# Fri3D_2024_00.net
KiCad netlist of a schematic drawn in Altium Designer
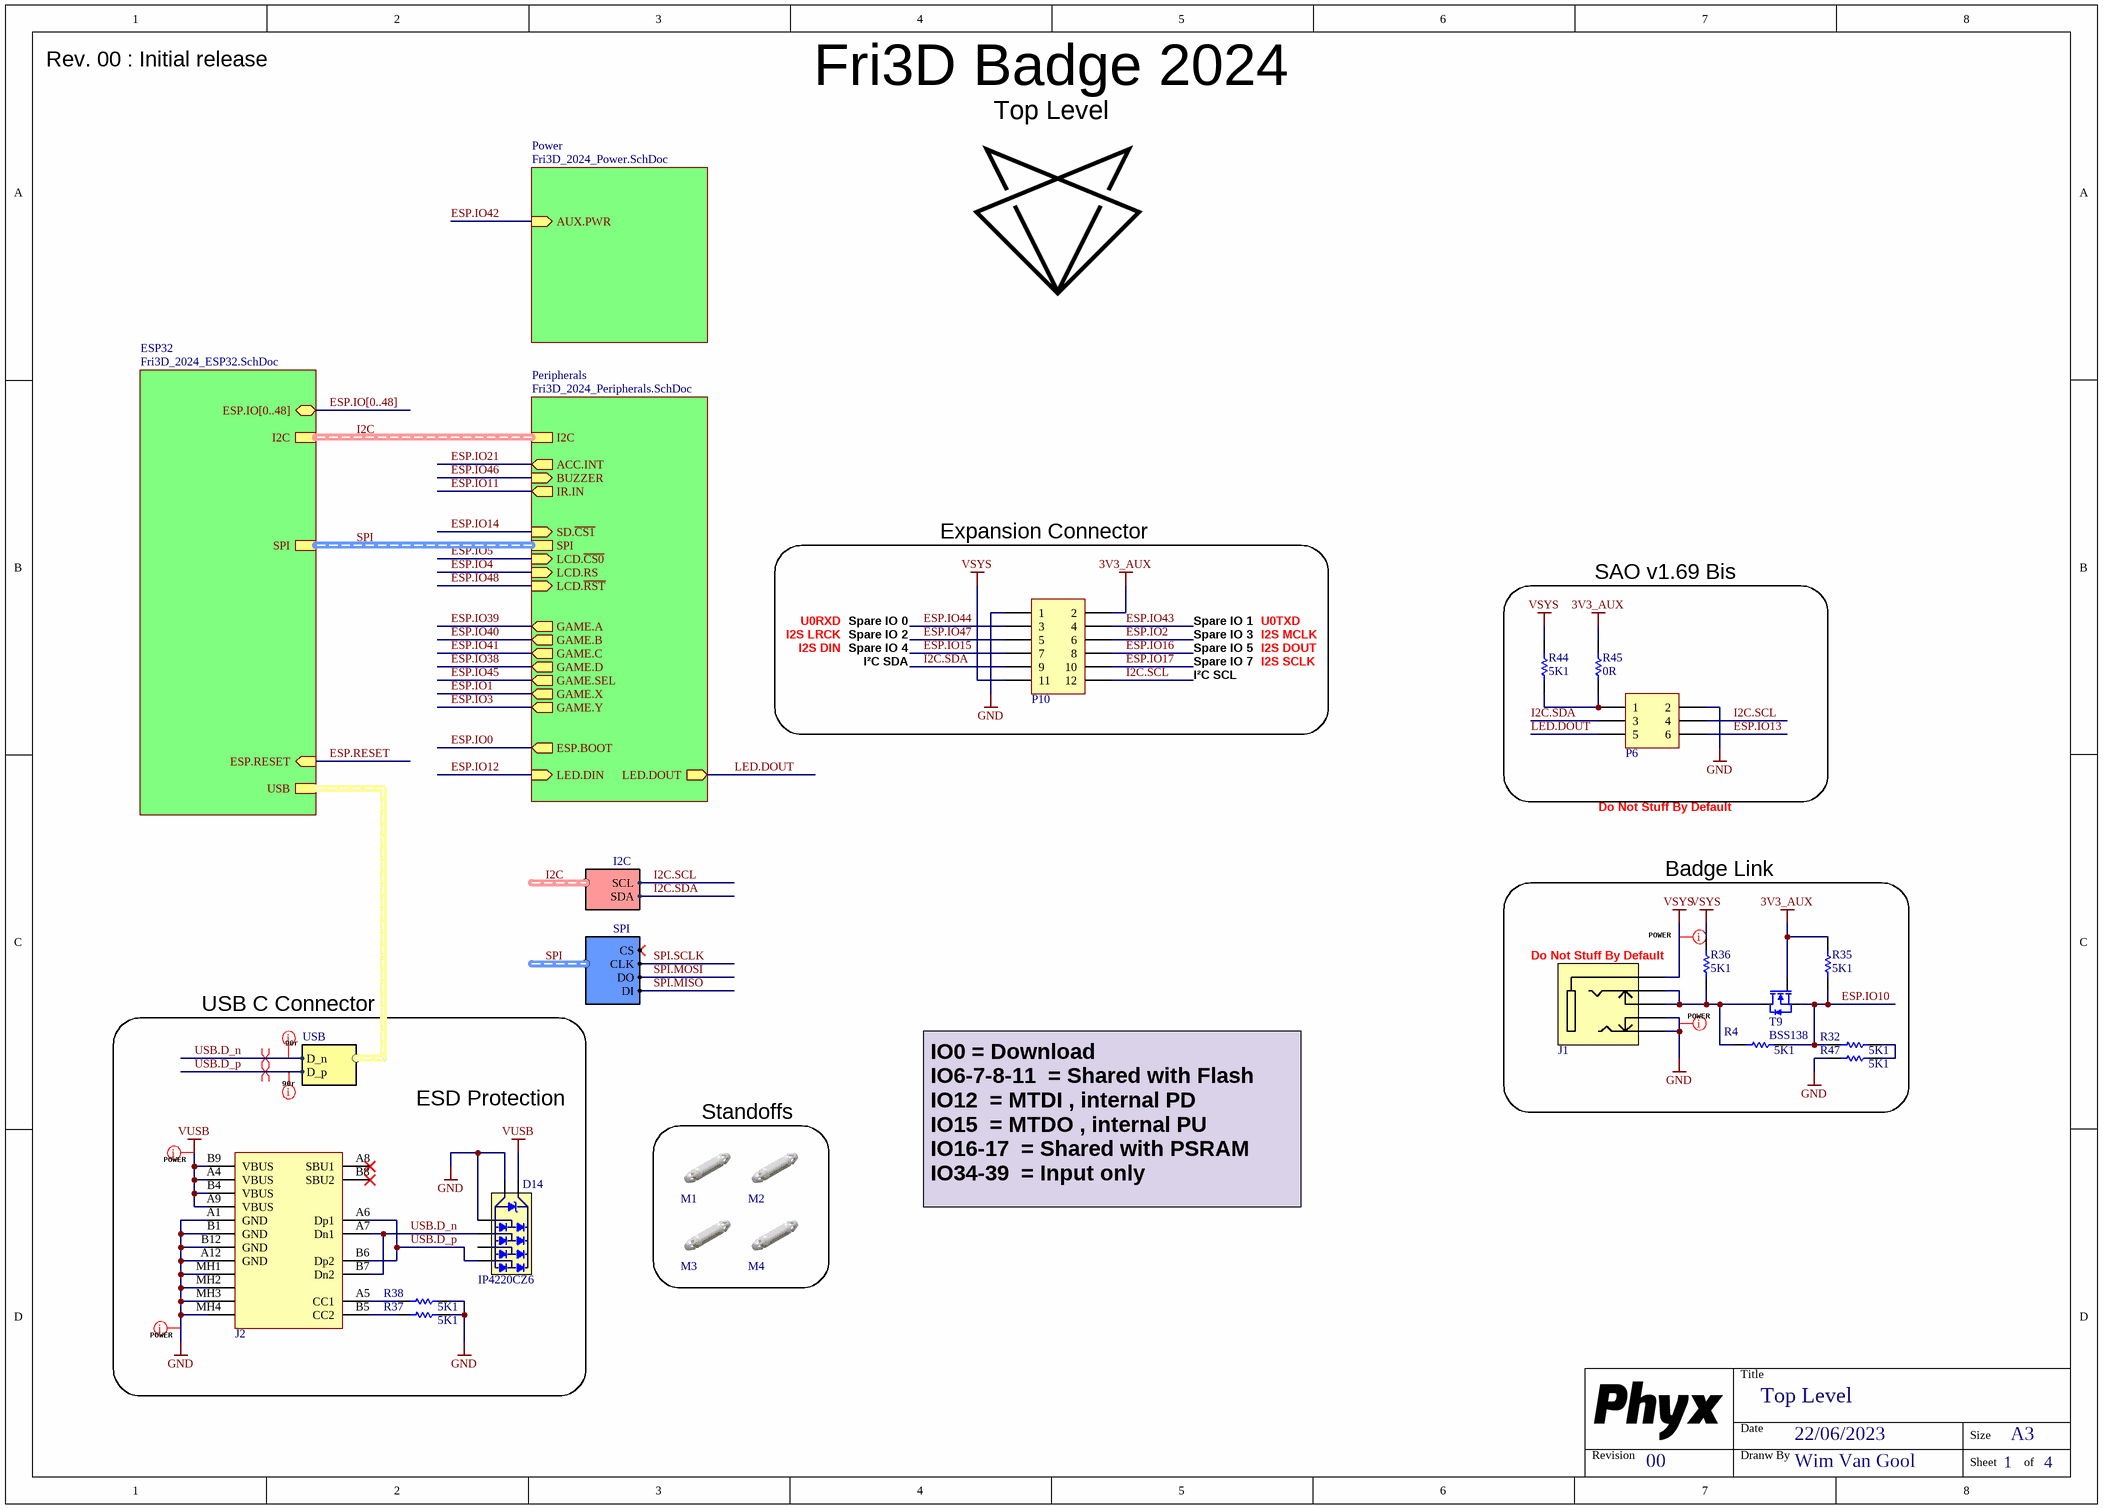
[diagram p0: Fri3D_2024_00.SchDoc]

(export (version "E")
  (design (tool "Eeschema 10.0.6"))
  (components
    (comp (ref "D14")
      (value "IP4220CZ6")
      (footprint "NXP_SOT457")
      (description "=Description")
      (fields (field (name "Comment") "TVS Diode Dual USB"))
      (libsource (lib "Phyx_Components") (part "NXP_IP4220CZ6"))
    )
    (comp (ref "J1")
      (value "3.5mm jack, dual switch, black, 3 contacts")
      (footprint "CUI_SJ1-3525NG")
      (description "=Description")
      (libsource (lib "Phyx_Components") (part "CUI_SJ1-3525NG"))
    )
    (comp (ref "J2")
      (value "USB 2.0 C Reversible Receptacle Horizontal full SMD")
      (footprint "XUNPU-TYPEC-304S-ACP16")
      (libsource (lib "Phyx_Components") (part "USB_C_16_4"))
    )
    (comp (ref "M1")
      (value "HIWA LCC-12 Snap-in - Snap-in 12.7mm")
      (footprint "WE_709622400")
      (description "SPACER SNAP-SNAP LCC-12 -12.7mm")
      (libsource (lib "Phyx_Components") (part "WE_SNSN"))
    )
    (comp (ref "M2")
      (value "HIWA LCC-12 Snap-in - Snap-in 12.7mm")
      (footprint "WE_709622400")
      (description "SPACER SNAP-SNAP LCC-12 -12.7mm")
      (libsource (lib "Phyx_Components") (part "WE_SNSN"))
    )
    (comp (ref "M3")
      (value "HIWA LCC-12 Snap-in - Snap-in 12.7mm")
      (footprint "WE_709622400")
      (description "SPACER SNAP-SNAP LCC-12 -12.7mm")
      (libsource (lib "Phyx_Components") (part "WE_SNSN"))
    )
    (comp (ref "M4")
      (value "HIWA LCC-12 Snap-in - Snap-in 12.7mm")
      (footprint "WE_709622400")
      (description "SPACER SNAP-SNAP LCC-12 -12.7mm")
      (libsource (lib "Phyx_Components") (part "WE_SNSN"))
    )
    (comp (ref "P6")
      (value "Receptacle 3x2")
      (footprint "RCPT2X3")
      (libsource (lib "Phyx_Components") (part "Header 3X2"))
    )
    (comp (ref "P10")
      (value "Receptacle 6x2 SMD low profile")
      (footprint "WE_610312243021_POST")
      (libsource (lib "Phyx_Components") (part "Header 6X2"))
    )
    (comp (ref "R4")
      (value "5K1")
      (footprint "R0603_N")
      (fields (field (name "Comment") "RESISTOR"))
      (libsource (lib "Phyx_Components") (part "RESISTOR"))
    )
    (comp (ref "R32")
      (value "5K1")
      (footprint "R0603_N")
      (fields (field (name "Comment") "RESISTOR"))
      (libsource (lib "Phyx_Components") (part "RESISTOR"))
    )
    (comp (ref "R35")
      (value "5K1")
      (footprint "R0603_N")
      (fields (field (name "Comment") "RESISTOR"))
      (libsource (lib "Phyx_Components") (part "RESISTOR"))
    )
    (comp (ref "R36")
      (value "5K1")
      (footprint "R0603_N")
      (fields (field (name "Comment") "RESISTOR"))
      (libsource (lib "Phyx_Components") (part "RESISTOR"))
    )
    (comp (ref "R37")
      (value "5K1")
      (footprint "R0603_N")
      (fields (field (name "Comment") "RESISTOR"))
      (libsource (lib "Phyx_Components") (part "RESISTOR"))
    )
    (comp (ref "R38")
      (value "5K1")
      (footprint "R0603_N")
      (fields (field (name "Comment") "RESISTOR"))
      (libsource (lib "Phyx_Components") (part "RESISTOR"))
    )
    (comp (ref "R44")
      (value "5K1")
      (footprint "R0603_N")
      (fields (field (name "Comment") "RESISTOR"))
      (libsource (lib "Phyx_Components") (part "RESISTOR"))
    )
    (comp (ref "R45")
      (value "0R")
      (footprint "R0603_N")
      (fields (field (name "Comment") "RESISTOR"))
      (libsource (lib "Phyx_Components") (part "RESISTOR"))
    )
    (comp (ref "R47")
      (value "5K1")
      (footprint "R0603_N")
      (fields (field (name "Comment") "RESISTOR"))
      (libsource (lib "Phyx_Components") (part "RESISTOR"))
    )
    (comp (ref "T9")
      (value "BSS138")
      (footprint "SOT23-3")
      (fields (field (name "Comment") "0.2A N-Ch MOSFET Vgs 3.2"))
      (libsource (lib "Phyx_Components") (part "N_MOSFET_GSD"))
    )
  )
  (nets
    (net (code "32") (name "/ESP.IO2") (class "Default")
      (node (ref "P10") (pin "6") (pinfunction "6_6") (pintype "passive"))
    )
    (net (code "36") (name "/ESP.IO10") (class "Default")
      (node (ref "R32") (pin "2") (pinfunction "2_2") (pintype "passive"))
      (node (ref "R35") (pin "2") (pinfunction "2_2") (pintype "passive"))
      (node (ref "R4") (pin "1") (pinfunction "1_1") (pintype "passive"))
      (node (ref "T9") (pin "2") (pinfunction "S_2") (pintype "passive"))
    )
    (net (code "39") (name "/ESP.IO13") (class "Default")
      (node (ref "P6") (pin "6") (pinfunction "6_6") (pintype "passive"))
    )
    (net (code "41") (name "/ESP.IO15") (class "Default")
      (node (ref "P10") (pin "7") (pinfunction "7_7") (pintype "passive"))
    )
    (net (code "42") (name "/ESP.IO16") (class "Default")
      (node (ref "P10") (pin "8") (pinfunction "8_8") (pintype "passive"))
    )
    (net (code "43") (name "/ESP.IO17") (class "Default")
      (node (ref "P10") (pin "10") (pinfunction "10_10") (pintype "passive"))
    )
    (net (code "50") (name "/ESP.IO43") (class "Default")
      (node (ref "P10") (pin "4") (pinfunction "4_4") (pintype "passive"))
    )
    (net (code "51") (name "/ESP.IO44") (class "Default")
      (node (ref "P10") (pin "3") (pinfunction "3_3") (pintype "passive"))
    )
    (net (code "54") (name "/ESP.IO47") (class "Default")
      (node (ref "P10") (pin "5") (pinfunction "5_5") (pintype "passive"))
    )
    (net (code "58") (name "/I2C.SCL") (class "Default")
      (node (ref "P10") (pin "12") (pinfunction "12_12") (pintype "passive"))
      (node (ref "P6") (pin "4") (pinfunction "4_4") (pintype "passive"))
    )
    (net (code "59") (name "/I2C.SDA") (class "Default")
      (node (ref "P10") (pin "9") (pinfunction "9_9") (pintype "passive"))
      (node (ref "P6") (pin "3") (pinfunction "3_3") (pintype "passive"))
    )
    (net (code "61") (name "/LED.DOUT") (class "Default")
      (node (ref "P6") (pin "5") (pinfunction "5_5") (pintype "passive"))
    )
    (net (code "66") (name "/USB.D_n") (class "Default")
      (node (ref "D14") (pin "1") (pinfunction "1_1") (pintype "passive"))
      (node (ref "J2") (pin "A7") (pinfunction "Dn1_A7") (pintype "passive"))
      (node (ref "J2") (pin "B7") (pinfunction "Dn2_B7") (pintype "passive"))
    )
    (net (code "67") (name "/USB.D_p") (class "Default")
      (node (ref "D14") (pin "6") (pinfunction "6_6") (pintype "passive"))
      (node (ref "J2") (pin "A6") (pinfunction "Dp1_A6") (pintype "passive"))
      (node (ref "J2") (pin "B6") (pinfunction "Dp2_B6") (pintype "passive"))
    )
    (net (code "71") (name "3V3_AUX") (class "Default")
      (node (ref "P10") (pin "2") (pinfunction "2_2") (pintype "passive"))
      (node (ref "R35") (pin "1") (pinfunction "1_1") (pintype "passive"))
      (node (ref "R45") (pin "1") (pinfunction "1_1") (pintype "passive"))
      (node (ref "T9") (pin "1") (pinfunction "G_1") (pintype "passive"))
    )
    (net (code "72") (name "GND") (class "Default")
      (node (ref "D14") (pin "2") (pinfunction "GND_2") (pintype "passive"))
      (node (ref "D14") (pin "3") (pinfunction "3_3") (pintype "passive"))
      (node (ref "J1") (pin "2") (pinfunction "Tip_2") (pintype "passive"))
      (node (ref "J1") (pin "4") (pinfunction "4_4") (pintype "passive"))
      (node (ref "J2") (pin "A1") (pinfunction "GND_A1") (pintype "passive"))
      (node (ref "J2") (pin "A12") (pinfunction "GND_A12") (pintype "passive"))
      (node (ref "J2") (pin "B1") (pinfunction "GND_B1") (pintype "passive"))
      (node (ref "J2") (pin "B12") (pinfunction "GND_B12") (pintype "passive"))
      (node (ref "J2") (pin "MH1") (pinfunction "Tab_MH1") (pintype "passive"))
      (node (ref "J2") (pin "MH2") (pinfunction "Tab_MH2") (pintype "passive"))
      (node (ref "J2") (pin "MH3") (pinfunction "Tab_MH3") (pintype "passive"))
      (node (ref "J2") (pin "MH4") (pinfunction "Tab_MH4") (pintype "passive"))
      (node (ref "P10") (pin "1") (pinfunction "1_1") (pintype "passive"))
      (node (ref "P6") (pin "2") (pinfunction "2_2") (pintype "passive"))
      (node (ref "R37") (pin "2") (pinfunction "2_2") (pintype "passive"))
      (node (ref "R38") (pin "2") (pinfunction "2_2") (pintype "passive"))
      (node (ref "R47") (pin "2") (pinfunction "2_2") (pintype "passive"))
    )
    (net (code "73") (name "Net-(J1-Ring)") (class "Default")
      (node (ref "J1") (pin "3") (pinfunction "Ring_3") (pintype "passive"))
      (node (ref "J1") (pin "5") (pinfunction "5_5") (pintype "passive"))
      (node (ref "R36") (pin "2") (pinfunction "2_2") (pintype "passive"))
      (node (ref "R4") (pin "2") (pinfunction "2_2") (pintype "passive"))
      (node (ref "T9") (pin "3") (pinfunction "D_3") (pintype "passive"))
    )
    (net (code "74") (name "Net-(J2-CC1)") (class "Default")
      (node (ref "J2") (pin "A5") (pinfunction "CC1_A5") (pintype "passive"))
      (node (ref "R38") (pin "1") (pinfunction "1_1") (pintype "passive"))
    )
    (net (code "75") (name "Net-(J2-CC2)") (class "Default")
      (node (ref "J2") (pin "B5") (pinfunction "CC2_B5") (pintype "passive"))
      (node (ref "R37") (pin "1") (pinfunction "1_1") (pintype "passive"))
    )
    (net (code "76") (name "Net-(P6-Pad1)") (class "Default")
      (node (ref "P6") (pin "1") (pinfunction "1_1") (pintype "passive"))
      (node (ref "R44") (pin "1") (pinfunction "1_1") (pintype "passive"))
      (node (ref "R45") (pin "2") (pinfunction "2_2") (pintype "passive"))
    )
    (net (code "77") (name "Net-(R32-Pad1)") (class "Default")
      (node (ref "R32") (pin "1") (pinfunction "1_1") (pintype "passive"))
      (node (ref "R47") (pin "1") (pinfunction "1_1") (pintype "passive"))
    )
    (net (code "78") (name "VSYS") (class "Default")
      (node (ref "J1") (pin "1") (pinfunction "Sleeve_1") (pintype "passive"))
      (node (ref "P10") (pin "11") (pinfunction "11_11") (pintype "passive"))
      (node (ref "R36") (pin "1") (pinfunction "1_1") (pintype "passive"))
      (node (ref "R44") (pin "2") (pinfunction "2_2") (pintype "passive"))
    )
    (net (code "79") (name "VUSB") (class "Default")
      (node (ref "D14") (pin "5") (pinfunction "VBus_5") (pintype "passive"))
      (node (ref "J2") (pin "A4") (pinfunction "VBUS_A4") (pintype "passive"))
      (node (ref "J2") (pin "A9") (pinfunction "VBUS_A9") (pintype "passive"))
      (node (ref "J2") (pin "B4") (pinfunction "VBUS_B4") (pintype "passive"))
      (node (ref "J2") (pin "B9") (pinfunction "VBUS_B9") (pintype "passive"))
    )
    (net (code "80") (name "unconnected-(D14-Pad4)") (class "Default")
      (node (ref "D14") (pin "4") (pinfunction "4_4") (pintype "passive"))
    )
    (net (code "81") (name "unconnected-(J2-SBU1-PadA8)") (class "Default")
      (node (ref "J2") (pin "A8") (pinfunction "SBU1_A8") (pintype "passive+no_connect"))
    )
    (net (code "82") (name "unconnected-(J2-SBU2-PadB8)") (class "Default")
      (node (ref "J2") (pin "B8") (pinfunction "SBU2_B8") (pintype "passive+no_connect"))
    )
  )
)
